# USBSocket_Type3_v1_0.net
KiCad netlist of a schematic drawn in EAGLE
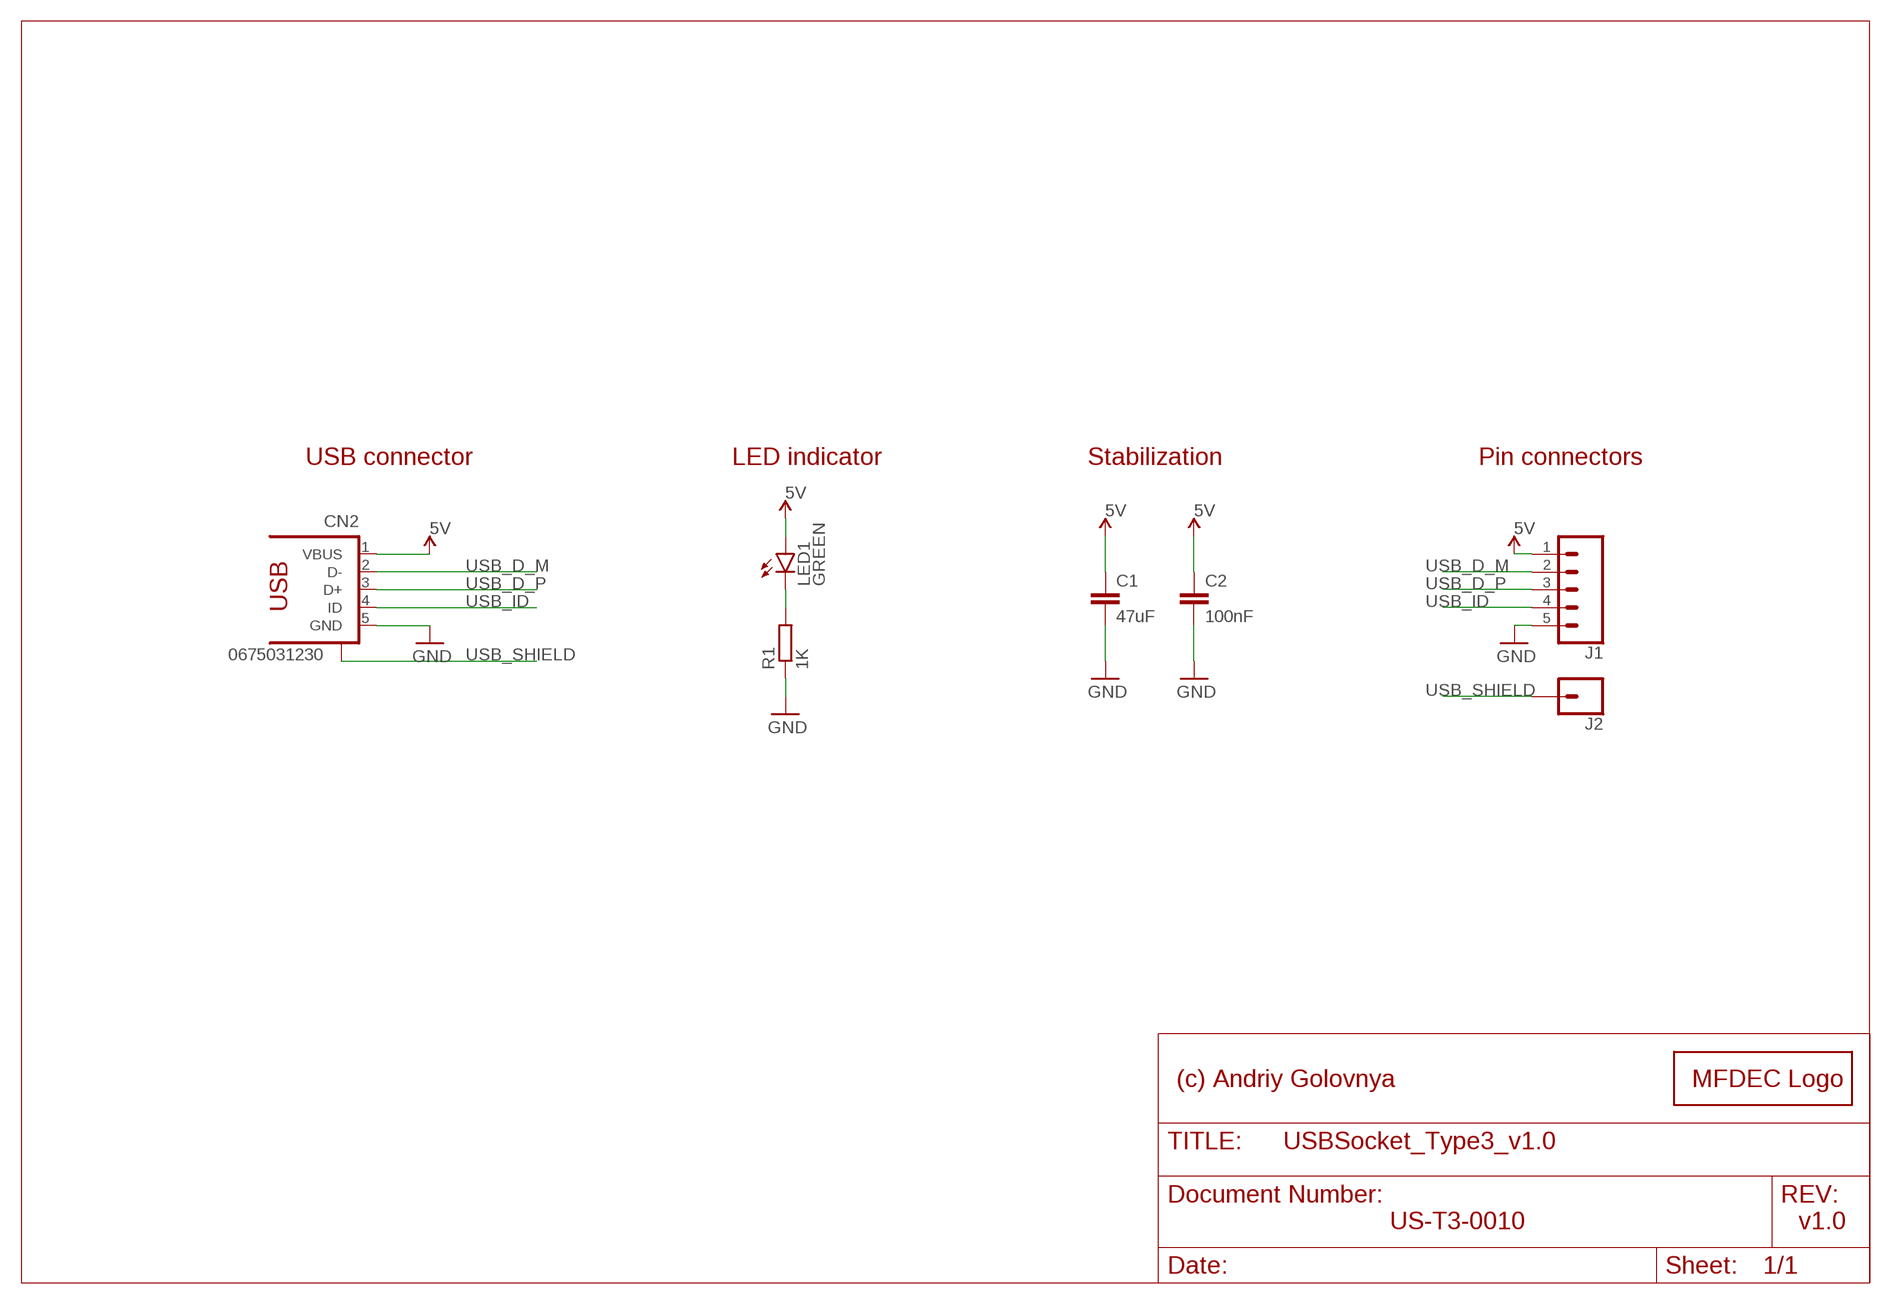
[diagram p0: schematic, sheet 1]

(export (version "E")
  (design (tool "Eeschema 10.0.6"))
  (components
    (comp (ref "C1")
      (value "47uF")
      (footprint "eagle-import:C0805")
      (libsource (lib "eagle-import") (part "C-EUC0805"))
    )
    (comp (ref "C2")
      (value "100nF")
      (footprint "eagle-import:C0402")
      (libsource (lib "eagle-import") (part "C-EUC0402"))
    )
    (comp (ref "CN2")
      (value "0675031230")
      (footprint "eagle-import:PMX42_56579-0576")
      (libsource (lib "eagle-import") (part "PMX42_56579-0576"))
    )
    (comp (ref "J1")
      (value "CONN_05PTH")
      (footprint "eagle-import:1X05")
      (libsource (lib "eagle-import") (part "CONN_05PTH"))
    )
    (comp (ref "J2")
      (value "CONN_01")
      (footprint "eagle-import:1X01")
      (libsource (lib "eagle-import") (part "CONN_01"))
    )
    (comp (ref "LED1")
      (value "GREEN")
      (footprint "eagle-import:SML0603")
      (libsource (lib "eagle-import") (part "LEDSML0603"))
    )
    (comp (ref "LOGO1")
      (value "MFDECLOGO_L_10MM")
      (footprint "eagle-import:MFDEC_L_10MM")
      (libsource (lib "eagle-import") (part "MFDECLOGO_L_10MM"))
    )
    (comp (ref "R1")
      (value "1K")
      (footprint "eagle-import:R0402")
      (libsource (lib "eagle-import") (part "R-EU_R0402"))
    )
  )
  (nets
    (net (code "1") (name "/USB_D_M") (class "Default")
      (node (ref "CN2") (pin "2") (pinfunction "D-_2") (pintype "passive"))
      (node (ref "J1") (pin "2") (pinfunction "2_2") (pintype "passive"))
    )
    (net (code "2") (name "/USB_D_P") (class "Default")
      (node (ref "CN2") (pin "3") (pinfunction "D+_3") (pintype "passive"))
      (node (ref "J1") (pin "3") (pinfunction "3_3") (pintype "passive"))
    )
    (net (code "3") (name "/USB_ID") (class "Default")
      (node (ref "CN2") (pin "4") (pinfunction "ID_4") (pintype "passive"))
      (node (ref "J1") (pin "4") (pinfunction "4_4") (pintype "passive"))
    )
    (net (code "4") (name "/USB_SHIELD") (class "Default")
      (node (ref "CN2") (pin "S1") (pinfunction "S_S1") (pintype "passive"))
      (node (ref "CN2") (pin "S2") (pinfunction "S_S2") (pintype "passive"))
      (node (ref "CN2") (pin "S3") (pinfunction "S_S3") (pintype "passive"))
      (node (ref "CN2") (pin "S4") (pinfunction "S_S4") (pintype "passive"))
      (node (ref "J2") (pin "1") (pinfunction "1_1") (pintype "passive"))
    )
    (net (code "5") (name "5V") (class "Default")
      (node (ref "C1") (pin "1") (pinfunction "1_1") (pintype "passive"))
      (node (ref "C2") (pin "1") (pinfunction "1_1") (pintype "passive"))
      (node (ref "CN2") (pin "1") (pinfunction "VBUS_1") (pintype "passive"))
      (node (ref "J1") (pin "1") (pinfunction "1_1") (pintype "passive"))
      (node (ref "LED1") (pin "A") (pinfunction "A_A") (pintype "passive"))
    )
    (net (code "6") (name "GND") (class "Default")
      (node (ref "C1") (pin "2") (pinfunction "2_2") (pintype "passive"))
      (node (ref "C2") (pin "2") (pinfunction "2_2") (pintype "passive"))
      (node (ref "CN2") (pin "5") (pinfunction "GND_5") (pintype "passive"))
      (node (ref "J1") (pin "5") (pinfunction "5_5") (pintype "passive"))
      (node (ref "R1") (pin "1") (pinfunction "1_1") (pintype "passive"))
    )
    (net (code "7") (name "Net-(LED1-PadC)") (class "Default")
      (node (ref "LED1") (pin "C") (pinfunction "C_C") (pintype "passive"))
      (node (ref "R1") (pin "2") (pinfunction "2_2") (pintype "passive"))
    )
  )
)
